# trezor_v1_1.net
KiCad netlist of a schematic drawn in EAGLE
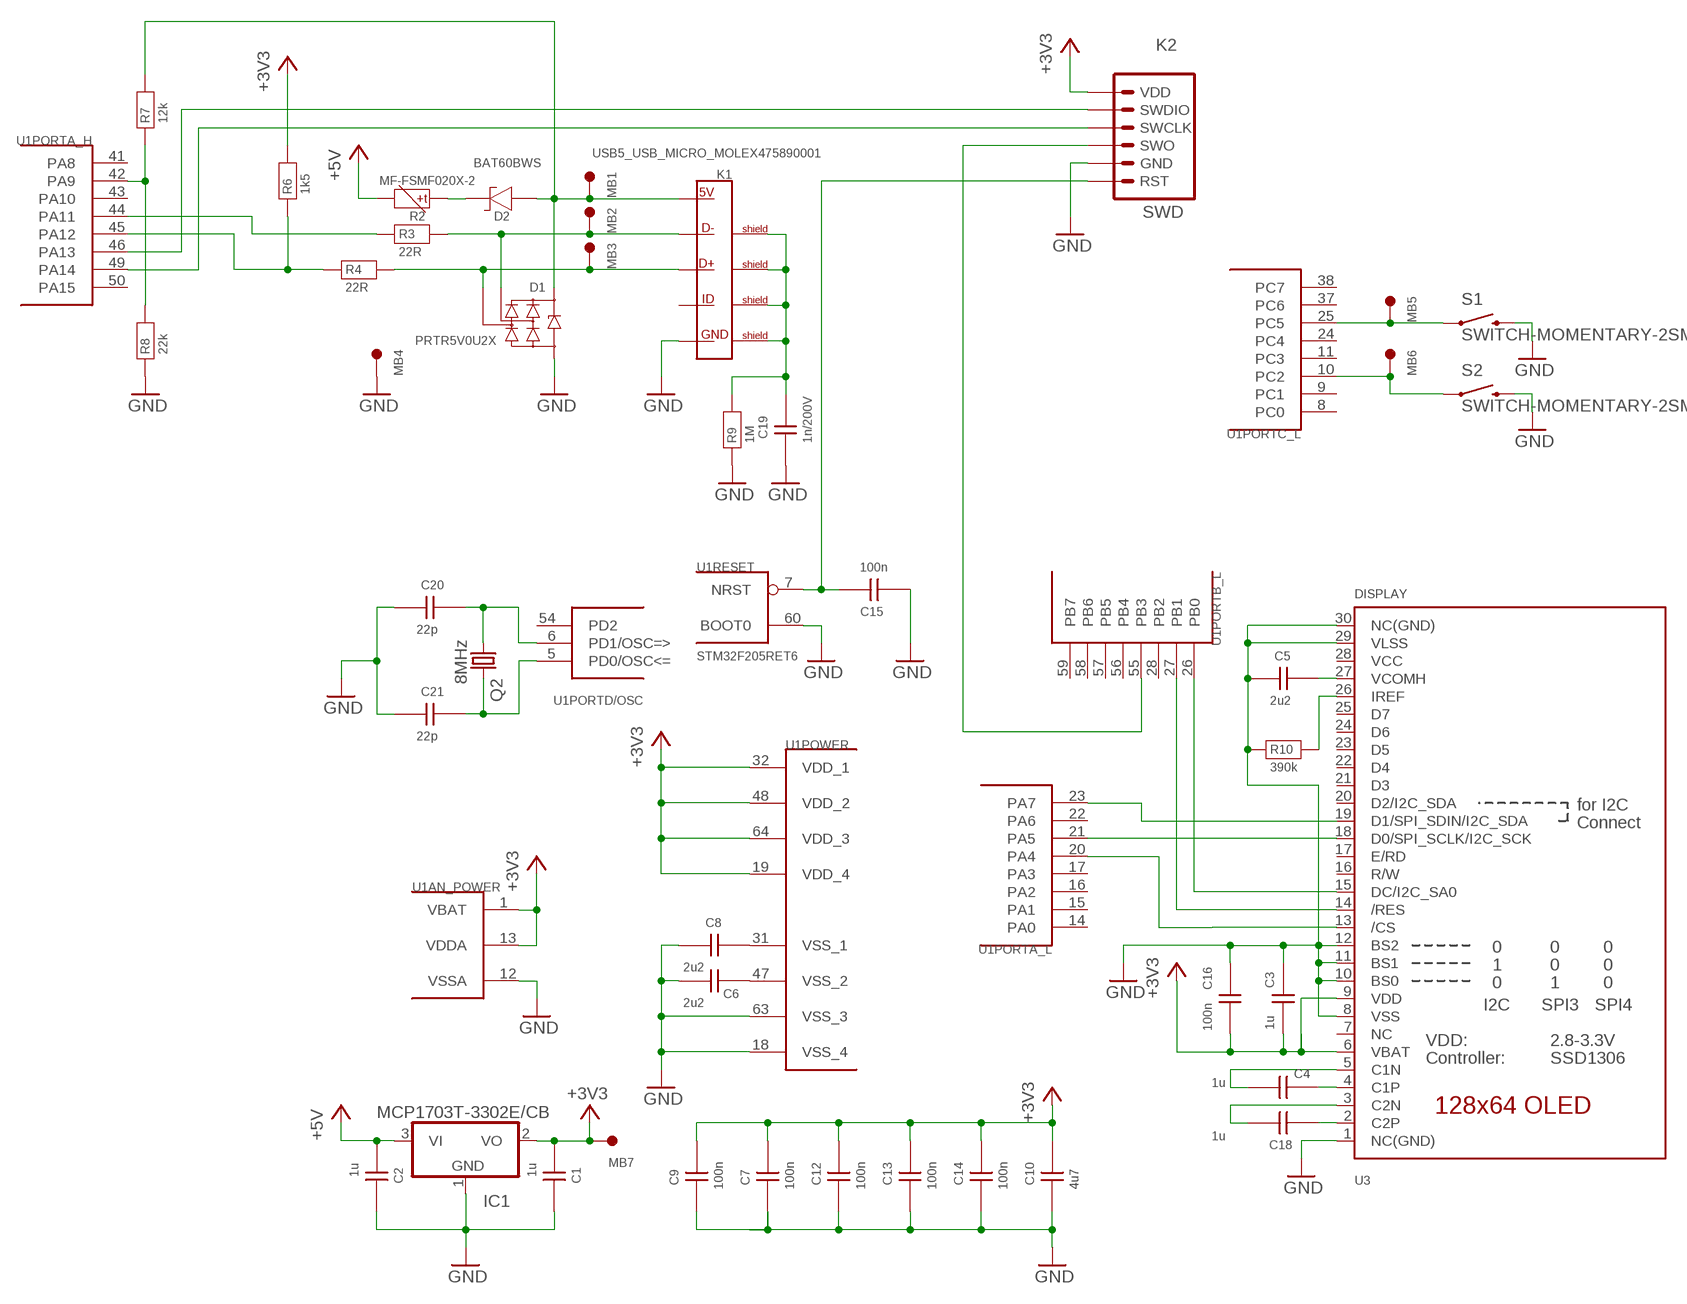
[diagram p0: schematic, sheet 1]

(export (version "E")
  (design (tool "Eeschema 10.0.6"))
  (components
    (comp (ref "C1")
      (value "1u")
      (footprint "eagle-import:0402")
      (libsource (lib "eagle-import") (part "C_0402"))
    )
    (comp (ref "C2")
      (value "1u")
      (footprint "eagle-import:0402")
      (libsource (lib "eagle-import") (part "C_0402"))
    )
    (comp (ref "C3")
      (value "1u")
      (footprint "eagle-import:0402")
      (libsource (lib "eagle-import") (part "C_0402"))
    )
    (comp (ref "C4")
      (value "1u")
      (footprint "eagle-import:0402")
      (libsource (lib "eagle-import") (part "C_0402"))
    )
    (comp (ref "C5")
      (value "2u2")
      (footprint "eagle-import:0603")
      (libsource (lib "eagle-import") (part "C_0603"))
    )
    (comp (ref "C6")
      (value "2u2")
      (footprint "eagle-import:0402")
      (libsource (lib "eagle-import") (part "C_0402"))
    )
    (comp (ref "C7")
      (value "100n")
      (footprint "eagle-import:0402")
      (libsource (lib "eagle-import") (part "C_0402"))
    )
    (comp (ref "C8")
      (value "2u2")
      (footprint "eagle-import:0402")
      (libsource (lib "eagle-import") (part "C_0402"))
    )
    (comp (ref "C9")
      (value "100n")
      (footprint "eagle-import:0402")
      (libsource (lib "eagle-import") (part "C_0402"))
    )
    (comp (ref "C10")
      (value "4u7")
      (footprint "eagle-import:0603")
      (libsource (lib "eagle-import") (part "C_0603"))
    )
    (comp (ref "C12")
      (value "100n")
      (footprint "eagle-import:0402")
      (libsource (lib "eagle-import") (part "C_0402"))
    )
    (comp (ref "C13")
      (value "100n")
      (footprint "eagle-import:0402")
      (libsource (lib "eagle-import") (part "C_0402"))
    )
    (comp (ref "C14")
      (value "100n")
      (footprint "eagle-import:0402")
      (libsource (lib "eagle-import") (part "C_0402"))
    )
    (comp (ref "C15")
      (value "100n")
      (footprint "eagle-import:0402")
      (libsource (lib "eagle-import") (part "C_0402"))
    )
    (comp (ref "C16")
      (value "100n")
      (footprint "eagle-import:0402")
      (libsource (lib "eagle-import") (part "C_0402"))
    )
    (comp (ref "C18")
      (value "1u")
      (footprint "eagle-import:0402")
      (libsource (lib "eagle-import") (part "C_0402"))
    )
    (comp (ref "C19")
      (value "1n/200V")
      (footprint "eagle-import:0603")
      (libsource (lib "eagle-import") (part "C_0603"))
    )
    (comp (ref "C20")
      (value "22p")
      (footprint "eagle-import:0402")
      (libsource (lib "eagle-import") (part "C_0402"))
    )
    (comp (ref "C21")
      (value "22p")
      (footprint "eagle-import:0402")
      (libsource (lib "eagle-import") (part "C_0402"))
    )
    (comp (ref "D1")
      (value "PRTR5V0U2X")
      (footprint "eagle-import:SOT143B")
      (libsource (lib "eagle-import") (part "PRTR5V0_SOT143B"))
    )
    (comp (ref "D2")
      (value "BAT60BWS")
      (footprint "eagle-import:SOD323")
      (libsource (lib "eagle-import") (part "DS_SOD323"))
    )
    (comp (ref "IC1")
      (value "MCP1703T-3302E/CB")
      (footprint "eagle-import:SOT23")
      (libsource (lib "eagle-import") (part "MCP1703CB"))
    )
    (comp (ref "K1")
      (value "USB5_USB_MICRO_MOLEX475890001")
      (footprint "eagle-import:USB_MICRO-MOLEX475890001")
      (libsource (lib "eagle-import") (part "USB5_USB_MICRO_MOLEX475890001"))
    )
    (comp (ref "K2")
      (value "SWD")
      (footprint "eagle-import:SWD")
      (libsource (lib "eagle-import") (part "SWD"))
    )
    (comp (ref "MB1")
      (value "MB_1.50")
      (footprint "eagle-import:MB1.5")
      (libsource (lib "eagle-import") (part "MB_1.50"))
    )
    (comp (ref "MB2")
      (value "MB_1.50")
      (footprint "eagle-import:MB1.5")
      (libsource (lib "eagle-import") (part "MB_1.50"))
    )
    (comp (ref "MB3")
      (value "MB_1.50")
      (footprint "eagle-import:MB1.5")
      (libsource (lib "eagle-import") (part "MB_1.50"))
    )
    (comp (ref "MB4")
      (value "MB_1.50")
      (footprint "eagle-import:MB1.5")
      (libsource (lib "eagle-import") (part "MB_1.50"))
    )
    (comp (ref "MB5")
      (value "MB_1.50")
      (footprint "eagle-import:MB1.5")
      (libsource (lib "eagle-import") (part "MB_1.50"))
    )
    (comp (ref "MB6")
      (value "MB_1.50")
      (footprint "eagle-import:MB1.5")
      (libsource (lib "eagle-import") (part "MB_1.50"))
    )
    (comp (ref "MB7")
      (value "MB_1.50")
      (footprint "eagle-import:MB1.5")
      (libsource (lib "eagle-import") (part "MB_1.50"))
    )
    (comp (ref "Q2")
      (value "8MHz")
      (footprint "eagle-import:CTS406")
      (libsource (lib "eagle-import") (part "CRYSTALCTS406"))
    )
    (comp (ref "R2")
      (value "MF-FSMF020X-2")
      (footprint "eagle-import:0603")
      (libsource (lib "eagle-import") (part "POLYSWITCH_0603"))
    )
    (comp (ref "R3")
      (value "22R")
      (footprint "eagle-import:0402")
      (libsource (lib "eagle-import") (part "R_0402"))
    )
    (comp (ref "R4")
      (value "22R")
      (footprint "eagle-import:0402")
      (libsource (lib "eagle-import") (part "R_0402"))
    )
    (comp (ref "R6")
      (value "1k5")
      (footprint "eagle-import:0402")
      (libsource (lib "eagle-import") (part "R_0402"))
    )
    (comp (ref "R7")
      (value "12k")
      (footprint "eagle-import:0402")
      (libsource (lib "eagle-import") (part "R_0402"))
    )
    (comp (ref "R8")
      (value "22k")
      (footprint "eagle-import:0402")
      (libsource (lib "eagle-import") (part "R_0402"))
    )
    (comp (ref "R9")
      (value "1M")
      (footprint "eagle-import:0603")
      (libsource (lib "eagle-import") (part "R_0603"))
    )
    (comp (ref "R10")
      (value "390k")
      (footprint "eagle-import:0402")
      (libsource (lib "eagle-import") (part "R_0402"))
    )
    (comp (ref "S1")
      (value "SWITCH-MOMENTARY-2SMD")
      (footprint "eagle-import:TACTILE_SWITCH_SMD")
      (libsource (lib "eagle-import") (part "SWITCH-MOMENTARY-2SMD"))
    )
    (comp (ref "S2")
      (value "SWITCH-MOMENTARY-2SMD")
      (footprint "eagle-import:TACTILE_SWITCH_SMD")
      (libsource (lib "eagle-import") (part "SWITCH-MOMENTARY-2SMD"))
    )
    (comp (ref "U1")
      (value "STM32F205RET6")
      (footprint "eagle-import:TQFP64")
      (libsource (lib "eagle-import") (part "STM32F10XRXT6"))
    )
    (comp (ref "U3")
      (value "DISPLAY")
      (footprint "eagle-import:UG-2864HSWEG01_0.96IN_WRAPAROUND")
      (libsource (lib "eagle-import") (part "DISP_OLED_UG-2864HSWEG010.96{dblquote}"))
    )
  )
  (nets
    (net (code "1") (name "+3V3") (class "Default")
      (node (ref "C1") (pin "P$1") (pinfunction "1_P$1") (pintype "passive"))
      (node (ref "C10") (pin "2") (pinfunction "2_2") (pintype "passive"))
      (node (ref "C12") (pin "P$2") (pinfunction "2_P$2") (pintype "passive"))
      (node (ref "C13") (pin "P$2") (pinfunction "2_P$2") (pintype "passive"))
      (node (ref "C14") (pin "P$2") (pinfunction "2_P$2") (pintype "passive"))
      (node (ref "C16") (pin "P$1") (pinfunction "1_P$1") (pintype "passive"))
      (node (ref "C3") (pin "P$1") (pinfunction "1_P$1") (pintype "passive"))
      (node (ref "C7") (pin "P$2") (pinfunction "2_P$2") (pintype "passive"))
      (node (ref "C9") (pin "P$2") (pinfunction "2_P$2") (pintype "passive"))
      (node (ref "IC1") (pin "2") (pinfunction "VO_2") (pintype "passive"))
      (node (ref "K2") (pin "6") (pinfunction "VDD_6") (pintype "passive"))
      (node (ref "MB7") (pin "1") (pinfunction "1_1") (pintype "passive"))
      (node (ref "R6") (pin "P$2") (pinfunction "2_P$2") (pintype "passive"))
      (node (ref "U1") (pin "1") (pinfunction "VBAT_1") (pintype "power_in"))
      (node (ref "U1") (pin "13") (pinfunction "VDDA_13") (pintype "power_in"))
      (node (ref "U1") (pin "19") (pinfunction "VDD_4_19") (pintype "power_in"))
      (node (ref "U1") (pin "32") (pinfunction "VDD_1_32") (pintype "power_in"))
      (node (ref "U1") (pin "48") (pinfunction "VDD_2_48") (pintype "power_in"))
      (node (ref "U1") (pin "64") (pinfunction "VDD_3_64") (pintype "power_in"))
      (node (ref "U3") (pin "6") (pinfunction "VBAT_6") (pintype "input"))
      (node (ref "U3") (pin "9") (pinfunction "VDD_9") (pintype "power_in"))
    )
    (net (code "2") (name "+5V") (class "Default")
      (node (ref "C2") (pin "P$1") (pinfunction "1_P$1") (pintype "passive"))
      (node (ref "IC1") (pin "3") (pinfunction "VI_3") (pintype "input"))
      (node (ref "R2") (pin "2") (pinfunction "2_2") (pintype "passive"))
    )
    (net (code "3") (name "/VCC") (class "Default")
      (node (ref "U3") (pin "28") (pinfunction "VCC_28") (pintype "power_in"))
    )
    (net (code "4") (name "GND") (class "Default")
      (node (ref "C1") (pin "P$2") (pinfunction "2_P$2") (pintype "passive"))
      (node (ref "C10") (pin "1") (pinfunction "1_1") (pintype "passive"))
      (node (ref "C12") (pin "P$1") (pinfunction "1_P$1") (pintype "passive"))
      (node (ref "C13") (pin "P$1") (pinfunction "1_P$1") (pintype "passive"))
      (node (ref "C14") (pin "P$1") (pinfunction "1_P$1") (pintype "passive"))
      (node (ref "C15") (pin "P$1") (pinfunction "1_P$1") (pintype "passive"))
      (node (ref "C16") (pin "P$2") (pinfunction "2_P$2") (pintype "passive"))
      (node (ref "C19") (pin "1") (pinfunction "1_1") (pintype "passive"))
      (node (ref "C2") (pin "P$2") (pinfunction "2_P$2") (pintype "passive"))
      (node (ref "C20") (pin "P$1") (pinfunction "1_P$1") (pintype "passive"))
      (node (ref "C21") (pin "P$1") (pinfunction "1_P$1") (pintype "passive"))
      (node (ref "C3") (pin "P$2") (pinfunction "2_P$2") (pintype "passive"))
      (node (ref "C5") (pin "1") (pinfunction "1_1") (pintype "passive"))
      (node (ref "C6") (pin "P$1") (pinfunction "1_P$1") (pintype "passive"))
      (node (ref "C7") (pin "P$1") (pinfunction "1_P$1") (pintype "passive"))
      (node (ref "C8") (pin "P$1") (pinfunction "1_P$1") (pintype "passive"))
      (node (ref "C9") (pin "P$1") (pinfunction "1_P$1") (pintype "passive"))
      (node (ref "D1") (pin "1") (pinfunction "GND_1") (pintype "passive"))
      (node (ref "IC1") (pin "1") (pinfunction "GND_1") (pintype "passive"))
      (node (ref "K1") (pin "5") (pinfunction "5_GND_5") (pintype "bidirectional"))
      (node (ref "K2") (pin "2") (pinfunction "GND_2") (pintype "passive"))
      (node (ref "MB4") (pin "1") (pinfunction "1_1") (pintype "passive"))
      (node (ref "R10") (pin "P$1") (pinfunction "1_P$1") (pintype "passive"))
      (node (ref "R8") (pin "P$1") (pinfunction "1_P$1") (pintype "passive"))
      (node (ref "R9") (pin "1") (pinfunction "1_1") (pintype "passive"))
      (node (ref "S1") (pin "3") (pinfunction "2_3") (pintype "passive"))
      (node (ref "S1") (pin "4") (pinfunction "2_4") (pintype "passive"))
      (node (ref "S2") (pin "3") (pinfunction "2_3") (pintype "passive"))
      (node (ref "S2") (pin "4") (pinfunction "2_4") (pintype "passive"))
      (node (ref "U1") (pin "12") (pinfunction "VSSA_12") (pintype "power_in"))
      (node (ref "U1") (pin "18") (pinfunction "VSS_4_18") (pintype "power_in"))
      (node (ref "U1") (pin "60") (pinfunction "BOOT0_60") (pintype "input"))
      (node (ref "U1") (pin "63") (pinfunction "VSS_3_63") (pintype "power_in"))
      (node (ref "U3") (pin "1") (pinfunction "NC(GND)_1") (pintype "input"))
      (node (ref "U3") (pin "10") (pinfunction "BS0_10") (pintype "input"))
      (node (ref "U3") (pin "11") (pinfunction "BS1_11") (pintype "input"))
      (node (ref "U3") (pin "12") (pinfunction "BS2_12") (pintype "input"))
      (node (ref "U3") (pin "29") (pinfunction "VLSS_29") (pintype "power_in"))
      (node (ref "U3") (pin "30") (pinfunction "NC(GND)_30") (pintype "input"))
      (node (ref "U3") (pin "8") (pinfunction "VSS_8") (pintype "power_in"))
    )
    (net (code "5") (name "Net-(C4-1)") (class "Default")
      (node (ref "C4") (pin "P$1") (pinfunction "1_P$1") (pintype "passive"))
      (node (ref "U3") (pin "4") (pinfunction "C1P_4") (pintype "input"))
    )
    (net (code "6") (name "Net-(C4-2)") (class "Default")
      (node (ref "C4") (pin "P$2") (pinfunction "2_P$2") (pintype "passive"))
      (node (ref "U3") (pin "5") (pinfunction "C1N_5") (pintype "input"))
    )
    (net (code "7") (name "Net-(C6-2)") (class "Default")
      (node (ref "C6") (pin "P$2") (pinfunction "2_P$2") (pintype "passive"))
      (node (ref "U1") (pin "47") (pinfunction "VSS_2_47") (pintype "power_in"))
    )
    (net (code "8") (name "Net-(C8-2)") (class "Default")
      (node (ref "C8") (pin "P$2") (pinfunction "2_P$2") (pintype "passive"))
      (node (ref "U1") (pin "31") (pinfunction "VSS_1_31") (pintype "power_in"))
    )
    (net (code "9") (name "Net-(C15-2)") (class "Default")
      (node (ref "C15") (pin "P$2") (pinfunction "2_P$2") (pintype "passive"))
      (node (ref "K2") (pin "1") (pinfunction "RST_1") (pintype "passive"))
      (node (ref "U1") (pin "7") (pinfunction "NRST_7") (pintype "input"))
    )
    (net (code "10") (name "Net-(C18-1)") (class "Default")
      (node (ref "C18") (pin "P$1") (pinfunction "1_P$1") (pintype "passive"))
      (node (ref "U3") (pin "2") (pinfunction "C2P_2") (pintype "input"))
    )
    (net (code "11") (name "Net-(C18-2)") (class "Default")
      (node (ref "C18") (pin "P$2") (pinfunction "2_P$2") (pintype "passive"))
      (node (ref "U3") (pin "3") (pinfunction "C2N_3") (pintype "input"))
    )
    (net (code "12") (name "Net-(C19-Pad2)") (class "Default")
      (node (ref "C19") (pin "2") (pinfunction "2_2") (pintype "passive"))
      (node (ref "K1") (pin "S1_BOT") (pinfunction "SHIELD_1_S1_BOT") (pintype "passive"))
      (node (ref "K1") (pin "S1_TOP") (pinfunction "SHIELD_1_S1_TOP") (pintype "passive"))
      (node (ref "K1") (pin "S2_BOT") (pinfunction "SHIELD_2_S2_BOT") (pintype "passive"))
      (node (ref "K1") (pin "S2_TOP") (pinfunction "SHIELD_2_S2_TOP") (pintype "passive"))
      (node (ref "K1") (pin "S3_BOT") (pinfunction "SHIELD_3_S3_BOT") (pintype "passive"))
      (node (ref "K1") (pin "S3_TOP") (pinfunction "SHIELD_3_S3_TOP") (pintype "passive"))
      (node (ref "K1") (pin "S4_BOT") (pinfunction "SHIELD_4_S4_BOT") (pintype "passive"))
      (node (ref "K1") (pin "S4_TOP") (pinfunction "SHIELD_4_S4_TOP") (pintype "passive"))
      (node (ref "K1") (pin "SA") (pinfunction "SHIELD_1_SA") (pintype "passive"))
      (node (ref "K1") (pin "SB") (pinfunction "SHIELD_2_SB") (pintype "passive"))
      (node (ref "R9") (pin "2") (pinfunction "2_2") (pintype "passive"))
    )
    (net (code "13") (name "Net-(C20-2)") (class "Default")
      (node (ref "C20") (pin "P$2") (pinfunction "2_P$2") (pintype "passive"))
      (node (ref "Q2") (pin "1") (pinfunction "1_1") (pintype "passive"))
      (node (ref "U1") (pin "6") (pinfunction "PD1/OSC=>_6") (pintype "bidirectional"))
    )
    (net (code "14") (name "Net-(C21-2)") (class "Default")
      (node (ref "C21") (pin "P$2") (pinfunction "2_P$2") (pintype "passive"))
      (node (ref "Q2") (pin "3") (pinfunction "2_3") (pintype "passive"))
      (node (ref "U1") (pin "5") (pinfunction "PD0/OSC<=_5") (pintype "bidirectional"))
    )
    (net (code "15") (name "Net-(D1-I{slash}O1)") (class "Default")
      (node (ref "D1") (pin "2") (pinfunction "I/O1_2") (pintype "passive"))
      (node (ref "K1") (pin "2") (pinfunction "2_D-_2") (pintype "bidirectional"))
      (node (ref "MB2") (pin "1") (pinfunction "1_1") (pintype "passive"))
      (node (ref "R3") (pin "P$2") (pinfunction "2_P$2") (pintype "passive"))
    )
    (net (code "16") (name "Net-(D1-I{slash}O2)") (class "Default")
      (node (ref "D1") (pin "3") (pinfunction "I/O2_3") (pintype "passive"))
      (node (ref "K1") (pin "3") (pinfunction "3_D+_3") (pintype "bidirectional"))
      (node (ref "MB3") (pin "1") (pinfunction "1_1") (pintype "passive"))
      (node (ref "R4") (pin "P$2") (pinfunction "2_P$2") (pintype "passive"))
    )
    (net (code "17") (name "Net-(D1-VCC)") (class "Default")
      (node (ref "D1") (pin "4") (pinfunction "VCC_4") (pintype "passive"))
      (node (ref "D2") (pin "A") (pinfunction "1_A") (pintype "passive"))
      (node (ref "K1") (pin "1") (pinfunction "1_5V_1") (pintype "bidirectional"))
      (node (ref "MB1") (pin "1") (pinfunction "1_1") (pintype "passive"))
      (node (ref "R7") (pin "P$2") (pinfunction "2_P$2") (pintype "passive"))
    )
    (net (code "18") (name "Net-(D2-2)") (class "Default")
      (node (ref "D2") (pin "K") (pinfunction "2_K") (pintype "passive"))
      (node (ref "R2") (pin "1") (pinfunction "1_1") (pintype "passive"))
    )
    (net (code "19") (name "Net-(K2-SWCLK)") (class "Default")
      (node (ref "K2") (pin "4") (pinfunction "SWCLK_4") (pintype "passive"))
      (node (ref "U1") (pin "49") (pinfunction "PA14_49") (pintype "bidirectional"))
    )
    (net (code "20") (name "Net-(K2-SWDIO)") (class "Default")
      (node (ref "K2") (pin "5") (pinfunction "SWDIO_5") (pintype "passive"))
      (node (ref "U1") (pin "46") (pinfunction "PA13_46") (pintype "bidirectional"))
    )
    (net (code "21") (name "Net-(K2-SWO)") (class "Default")
      (node (ref "K2") (pin "3") (pinfunction "SWO_3") (pintype "passive"))
      (node (ref "U1") (pin "55") (pinfunction "PB3_55") (pintype "bidirectional"))
    )
    (net (code "22") (name "Net-(R3-1)") (class "Default")
      (node (ref "R3") (pin "P$1") (pinfunction "1_P$1") (pintype "passive"))
      (node (ref "U1") (pin "44") (pinfunction "PA11_44") (pintype "bidirectional"))
    )
    (net (code "23") (name "Net-(R4-1)") (class "Default")
      (node (ref "R4") (pin "P$1") (pinfunction "1_P$1") (pintype "passive"))
      (node (ref "R6") (pin "P$1") (pinfunction "1_P$1") (pintype "passive"))
      (node (ref "U1") (pin "45") (pinfunction "PA12_45") (pintype "bidirectional"))
    )
    (net (code "24") (name "Net-(R7-1)") (class "Default")
      (node (ref "R7") (pin "P$1") (pinfunction "1_P$1") (pintype "passive"))
      (node (ref "R8") (pin "P$2") (pinfunction "2_P$2") (pintype "passive"))
      (node (ref "U1") (pin "42") (pinfunction "PA9_42") (pintype "bidirectional"))
    )
    (net (code "25") (name "Net-(R10-2)") (class "Default")
      (node (ref "R10") (pin "P$2") (pinfunction "2_P$2") (pintype "passive"))
      (node (ref "U3") (pin "26") (pinfunction "IREF_26") (pintype "input"))
    )
    (net (code "26") (name "Net-(U1C-PA4)") (class "Default")
      (node (ref "U1") (pin "20") (pinfunction "PA4_20") (pintype "bidirectional"))
      (node (ref "U3") (pin "13") (pinfunction "/CS_13") (pintype "input"))
    )
    (net (code "27") (name "Net-(U1C-PA5)") (class "Default")
      (node (ref "U1") (pin "21") (pinfunction "PA5_21") (pintype "bidirectional"))
      (node (ref "U3") (pin "18") (pinfunction "D0/SPI_SCLK/I2C_SCK_18") (pintype "bidirectional"))
    )
    (net (code "28") (name "Net-(U1C-PA7)") (class "Default")
      (node (ref "U1") (pin "23") (pinfunction "PA7_23") (pintype "bidirectional"))
      (node (ref "U3") (pin "19") (pinfunction "D1/SPI_SDIN/I2C_SDA_19") (pintype "bidirectional"))
    )
    (net (code "29") (name "Net-(U1E-PB0)") (class "Default")
      (node (ref "U1") (pin "26") (pinfunction "PB0_26") (pintype "bidirectional"))
      (node (ref "U3") (pin "15") (pinfunction "DC/I2C_SA0_15") (pintype "input"))
    )
    (net (code "30") (name "Net-(U1E-PB1)") (class "Default")
      (node (ref "U1") (pin "27") (pinfunction "PB1_27") (pintype "bidirectional"))
      (node (ref "U3") (pin "14") (pinfunction "/RES_14") (pintype "input"))
    )
    (net (code "31") (name "Net-(U1G-PC2)") (class "Default")
      (node (ref "MB6") (pin "1") (pinfunction "1_1") (pintype "passive"))
      (node (ref "S2") (pin "1") (pinfunction "1_1") (pintype "passive"))
      (node (ref "S2") (pin "2") (pinfunction "1_2") (pintype "passive"))
      (node (ref "U1") (pin "10") (pinfunction "PC2_10") (pintype "bidirectional"))
    )
    (net (code "32") (name "Net-(U1G-PC5)") (class "Default")
      (node (ref "MB5") (pin "1") (pinfunction "1_1") (pintype "passive"))
      (node (ref "S1") (pin "1") (pinfunction "1_1") (pintype "passive"))
      (node (ref "S1") (pin "2") (pinfunction "1_2") (pintype "passive"))
      (node (ref "U1") (pin "25") (pinfunction "PC5_25") (pintype "bidirectional"))
    )
    (net (code "33") (name "Net-(U3-VCOMH)") (class "Default")
      (node (ref "C5") (pin "2") (pinfunction "2_2") (pintype "passive"))
      (node (ref "U3") (pin "27") (pinfunction "VCOMH_27") (pintype "output"))
    )
    (net (code "34") (name "unconnected-(K1-4_ID-Pad4)") (class "Default")
      (node (ref "K1") (pin "4") (pinfunction "4_ID_4") (pintype "bidirectional"))
    )
    (net (code "35") (name "unconnected-(U1B-PA8-Pad41)") (class "Default")
      (node (ref "U1") (pin "41") (pinfunction "PA8_41") (pintype "bidirectional"))
    )
    (net (code "36") (name "unconnected-(U1B-PA10-Pad43)") (class "Default")
      (node (ref "U1") (pin "43") (pinfunction "PA10_43") (pintype "bidirectional"))
    )
    (net (code "37") (name "unconnected-(U1B-PA15-Pad50)") (class "Default")
      (node (ref "U1") (pin "50") (pinfunction "PA15_50") (pintype "bidirectional"))
    )
    (net (code "38") (name "unconnected-(U1C-PA0-Pad14)") (class "Default")
      (node (ref "U1") (pin "14") (pinfunction "PA0_14") (pintype "bidirectional"))
    )
    (net (code "39") (name "unconnected-(U1C-PA1-Pad15)") (class "Default")
      (node (ref "U1") (pin "15") (pinfunction "PA1_15") (pintype "bidirectional"))
    )
    (net (code "40") (name "unconnected-(U1C-PA2-Pad16)") (class "Default")
      (node (ref "U1") (pin "16") (pinfunction "PA2_16") (pintype "bidirectional"))
    )
    (net (code "41") (name "unconnected-(U1C-PA3-Pad17)") (class "Default")
      (node (ref "U1") (pin "17") (pinfunction "PA3_17") (pintype "bidirectional"))
    )
    (net (code "42") (name "unconnected-(U1C-PA6-Pad22)") (class "Default")
      (node (ref "U1") (pin "22") (pinfunction "PA6_22") (pintype "bidirectional"))
    )
    (net (code "43") (name "unconnected-(U1E-PB2-Pad28)") (class "Default")
      (node (ref "U1") (pin "28") (pinfunction "PB2_28") (pintype "bidirectional"))
    )
    (net (code "44") (name "unconnected-(U1E-PB4-Pad56)") (class "Default")
      (node (ref "U1") (pin "56") (pinfunction "PB4_56") (pintype "bidirectional"))
    )
    (net (code "45") (name "unconnected-(U1E-PB5-Pad57)") (class "Default")
      (node (ref "U1") (pin "57") (pinfunction "PB5_57") (pintype "bidirectional"))
    )
    (net (code "46") (name "unconnected-(U1E-PB6-Pad58)") (class "Default")
      (node (ref "U1") (pin "58") (pinfunction "PB6_58") (pintype "bidirectional"))
    )
    (net (code "47") (name "unconnected-(U1E-PB7-Pad59)") (class "Default")
      (node (ref "U1") (pin "59") (pinfunction "PB7_59") (pintype "bidirectional"))
    )
    (net (code "48") (name "unconnected-(U1G-PC0-Pad8)") (class "Default")
      (node (ref "U1") (pin "8") (pinfunction "PC0_8") (pintype "bidirectional"))
    )
    (net (code "49") (name "unconnected-(U1G-PC1-Pad9)") (class "Default")
      (node (ref "U1") (pin "9") (pinfunction "PC1_9") (pintype "bidirectional"))
    )
    (net (code "50") (name "unconnected-(U1G-PC3-Pad11)") (class "Default")
      (node (ref "U1") (pin "11") (pinfunction "PC3_11") (pintype "bidirectional"))
    )
    (net (code "51") (name "unconnected-(U1G-PC4-Pad24)") (class "Default")
      (node (ref "U1") (pin "24") (pinfunction "PC4_24") (pintype "bidirectional"))
    )
    (net (code "52") (name "unconnected-(U1G-PC6-Pad37)") (class "Default")
      (node (ref "U1") (pin "37") (pinfunction "PC6_37") (pintype "bidirectional"))
    )
    (net (code "53") (name "unconnected-(U1G-PC7-Pad38)") (class "Default")
      (node (ref "U1") (pin "38") (pinfunction "PC7_38") (pintype "bidirectional"))
    )
    (net (code "54") (name "unconnected-(U1H-PD2-Pad54)") (class "Default")
      (node (ref "U1") (pin "54") (pinfunction "PD2_54") (pintype "bidirectional"))
    )
    (net (code "55") (name "unconnected-(U3-D2{slash}I2C_SDA-Pad20)") (class "Default")
      (node (ref "U3") (pin "20") (pinfunction "D2/I2C_SDA_20") (pintype "bidirectional"))
    )
    (net (code "56") (name "unconnected-(U3-D3-Pad21)") (class "Default")
      (node (ref "U3") (pin "21") (pinfunction "D3_21") (pintype "bidirectional"))
    )
    (net (code "57") (name "unconnected-(U3-D4-Pad22)") (class "Default")
      (node (ref "U3") (pin "22") (pinfunction "D4_22") (pintype "bidirectional"))
    )
    (net (code "58") (name "unconnected-(U3-D5-Pad23)") (class "Default")
      (node (ref "U3") (pin "23") (pinfunction "D5_23") (pintype "bidirectional"))
    )
    (net (code "59") (name "unconnected-(U3-D6-Pad24)") (class "Default")
      (node (ref "U3") (pin "24") (pinfunction "D6_24") (pintype "bidirectional"))
    )
    (net (code "60") (name "unconnected-(U3-D7-Pad25)") (class "Default")
      (node (ref "U3") (pin "25") (pinfunction "D7_25") (pintype "bidirectional"))
    )
    (net (code "61") (name "unconnected-(U3-E{slash}RD-Pad17)") (class "Default")
      (node (ref "U3") (pin "17") (pinfunction "E/RD_17") (pintype "input"))
    )
    (net (code "62") (name "unconnected-(U3-NC-Pad7)") (class "Default")
      (node (ref "U3") (pin "7") (pinfunction "NC_7") (pintype "no_connect"))
    )
    (net (code "63") (name "unconnected-(U3-R{slash}W-Pad16)") (class "Default")
      (node (ref "U3") (pin "16") (pinfunction "R/W_16") (pintype "input"))
    )
  )
)
